# tmc2209.net
KiCad netlist of a schematic drawn in EAGLE
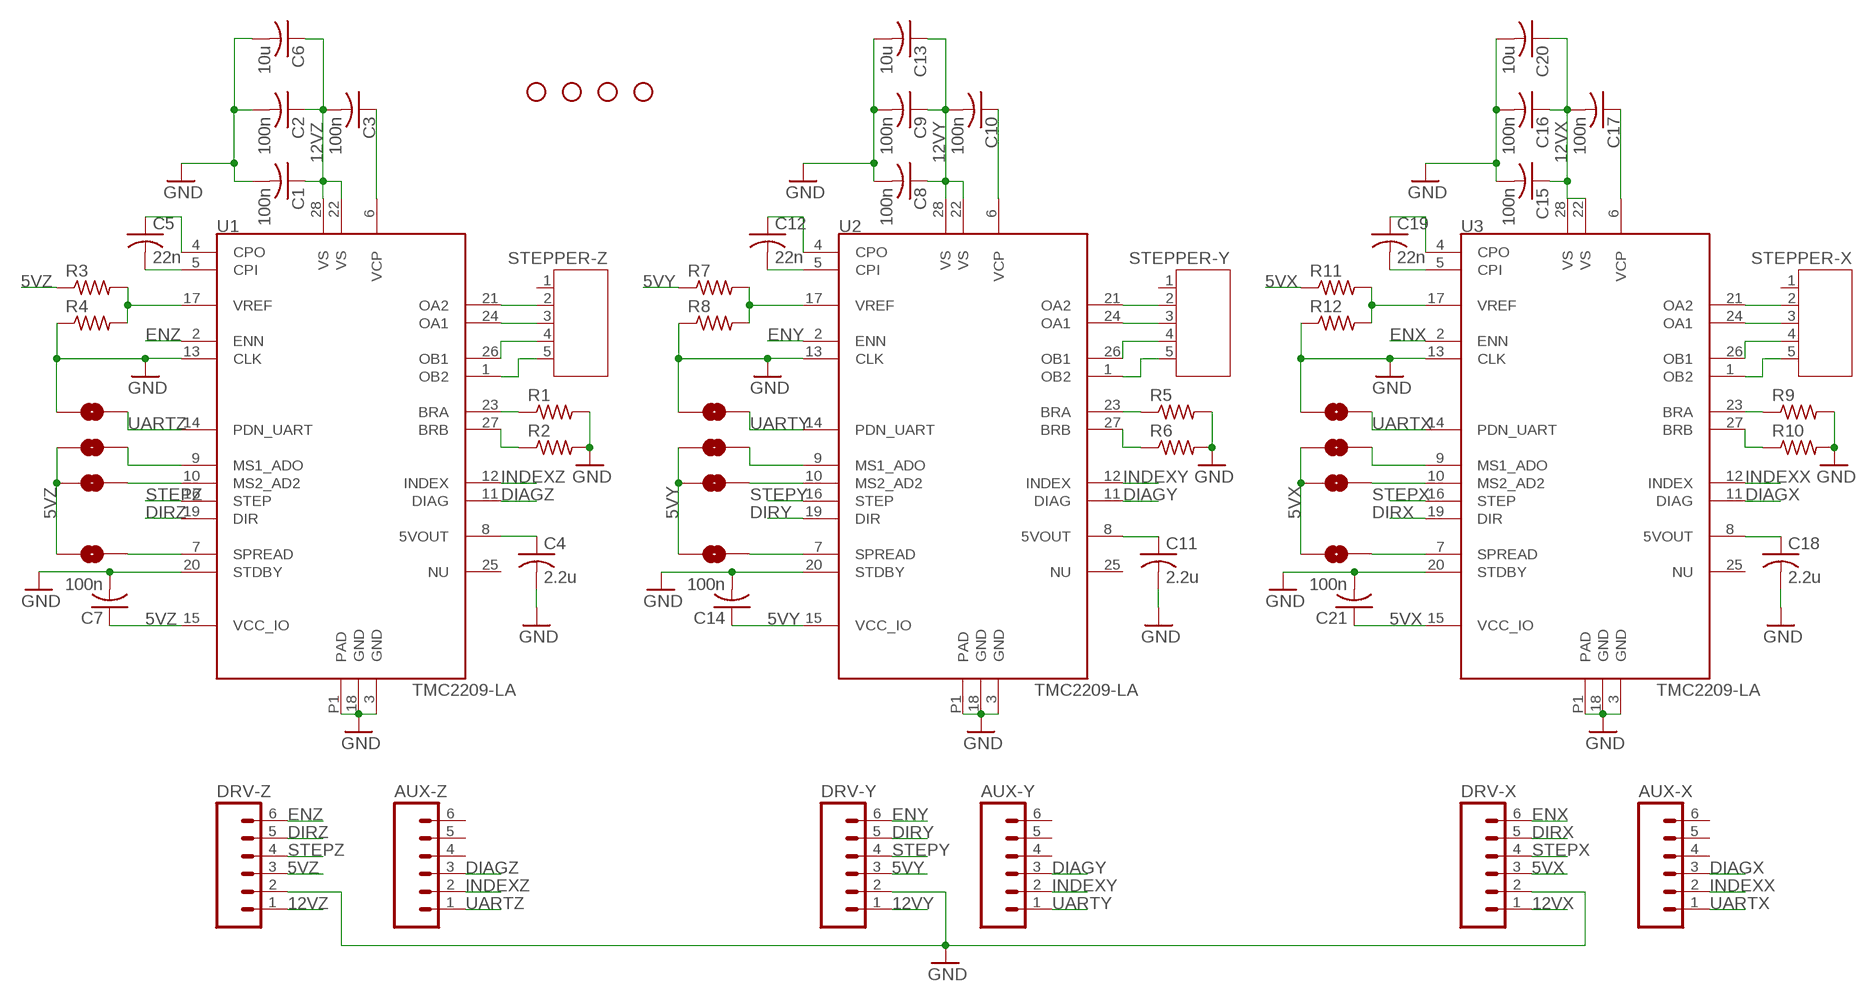
[diagram p0: schematic, sheet 1]

(export (version "E")
  (design (tool "Eeschema 10.0.6"))
  (components
    (comp (ref "AUX-X")
      (value "M06LOCK")
      (footprint "eagle-import:1X06_LOCK")
      (libsource (lib "eagle-import") (part "M06LOCK"))
    )
    (comp (ref "AUX-Y")
      (value "M06LOCK")
      (footprint "eagle-import:1X06_LOCK")
      (libsource (lib "eagle-import") (part "M06LOCK"))
    )
    (comp (ref "AUX-Z")
      (value "M06LOCK")
      (footprint "eagle-import:1X06_LOCK")
      (libsource (lib "eagle-import") (part "M06LOCK"))
    )
    (comp (ref "C1")
      (value "100n")
      (footprint "eagle-import:C0603")
      (libsource (lib "eagle-import") (part "C-USC0603"))
    )
    (comp (ref "C2")
      (value "100n")
      (footprint "eagle-import:C0603")
      (libsource (lib "eagle-import") (part "C-USC0603"))
    )
    (comp (ref "C3")
      (value "100n")
      (footprint "eagle-import:C0603")
      (libsource (lib "eagle-import") (part "C-USC0603"))
    )
    (comp (ref "C4")
      (value "2.2u")
      (footprint "eagle-import:C1206")
      (libsource (lib "eagle-import") (part "C-USC1206"))
    )
    (comp (ref "C5")
      (value "22n")
      (footprint "eagle-import:C0603")
      (libsource (lib "eagle-import") (part "C-USC0603"))
    )
    (comp (ref "C6")
      (value "10u")
      (footprint "eagle-import:C1206")
      (libsource (lib "eagle-import") (part "C-USC1206"))
    )
    (comp (ref "C7")
      (value "100n")
      (footprint "eagle-import:C0603")
      (libsource (lib "eagle-import") (part "C-USC0603"))
    )
    (comp (ref "C8")
      (value "100n")
      (footprint "eagle-import:C0603")
      (libsource (lib "eagle-import") (part "C-USC0603"))
    )
    (comp (ref "C9")
      (value "100n")
      (footprint "eagle-import:C0603")
      (libsource (lib "eagle-import") (part "C-USC0603"))
    )
    (comp (ref "C10")
      (value "100n")
      (footprint "eagle-import:C0603")
      (libsource (lib "eagle-import") (part "C-USC0603"))
    )
    (comp (ref "C11")
      (value "2.2u")
      (footprint "eagle-import:C1206")
      (libsource (lib "eagle-import") (part "C-USC1206"))
    )
    (comp (ref "C12")
      (value "22n")
      (footprint "eagle-import:C0603")
      (libsource (lib "eagle-import") (part "C-USC0603"))
    )
    (comp (ref "C13")
      (value "10u")
      (footprint "eagle-import:C1206")
      (libsource (lib "eagle-import") (part "C-USC1206"))
    )
    (comp (ref "C14")
      (value "100n")
      (footprint "eagle-import:C0603")
      (libsource (lib "eagle-import") (part "C-USC0603"))
    )
    (comp (ref "C15")
      (value "100n")
      (footprint "eagle-import:C0603")
      (libsource (lib "eagle-import") (part "C-USC0603"))
    )
    (comp (ref "C16")
      (value "100n")
      (footprint "eagle-import:C0603")
      (libsource (lib "eagle-import") (part "C-USC0603"))
    )
    (comp (ref "C17")
      (value "100n")
      (footprint "eagle-import:C0603")
      (libsource (lib "eagle-import") (part "C-USC0603"))
    )
    (comp (ref "C18")
      (value "2.2u")
      (footprint "eagle-import:C1206")
      (libsource (lib "eagle-import") (part "C-USC1206"))
    )
    (comp (ref "C19")
      (value "22n")
      (footprint "eagle-import:C0603")
      (libsource (lib "eagle-import") (part "C-USC0603"))
    )
    (comp (ref "C20")
      (value "10u")
      (footprint "eagle-import:C1206")
      (libsource (lib "eagle-import") (part "C-USC1206"))
    )
    (comp (ref "C21")
      (value "100n")
      (footprint "eagle-import:C0603")
      (libsource (lib "eagle-import") (part "C-USC0603"))
    )
    (comp (ref "DRV-X")
      (value "M06LOCK")
      (footprint "eagle-import:1X06_LOCK")
      (libsource (lib "eagle-import") (part "M06LOCK"))
    )
    (comp (ref "DRV-Y")
      (value "M06LOCK")
      (footprint "eagle-import:1X06_LOCK")
      (libsource (lib "eagle-import") (part "M06LOCK"))
    )
    (comp (ref "DRV-Z")
      (value "M06LOCK")
      (footprint "eagle-import:1X06_LOCK")
      (libsource (lib "eagle-import") (part "M06LOCK"))
    )
    (comp (ref "PDX")
      (value "SOLDERJUMPERNO")
      (footprint "eagle-import:SJ_2S-NO")
      (libsource (lib "eagle-import") (part "SOLDERJUMPERNO"))
    )
    (comp (ref "PDY")
      (value "SOLDERJUMPERNO")
      (footprint "eagle-import:SJ_2S-NO")
      (libsource (lib "eagle-import") (part "SOLDERJUMPERNO"))
    )
    (comp (ref "PDZ")
      (value "SOLDERJUMPERNO")
      (footprint "eagle-import:SJ_2S-NO")
      (libsource (lib "eagle-import") (part "SOLDERJUMPERNO"))
    )
    (comp (ref "R1")
      (value "R-US_R0805")
      (footprint "eagle-import:R0805")
      (libsource (lib "eagle-import") (part "R-US_R0805"))
    )
    (comp (ref "R2")
      (value "R-US_R0805")
      (footprint "eagle-import:R0805")
      (libsource (lib "eagle-import") (part "R-US_R0805"))
    )
    (comp (ref "R3")
      (value "R-US_R0603")
      (footprint "eagle-import:R0603")
      (libsource (lib "eagle-import") (part "R-US_R0603"))
    )
    (comp (ref "R4")
      (value "R-US_R0603")
      (footprint "eagle-import:R0603")
      (libsource (lib "eagle-import") (part "R-US_R0603"))
    )
    (comp (ref "R5")
      (value "R-US_R0805")
      (footprint "eagle-import:R0805")
      (libsource (lib "eagle-import") (part "R-US_R0805"))
    )
    (comp (ref "R6")
      (value "R-US_R0805")
      (footprint "eagle-import:R0805")
      (libsource (lib "eagle-import") (part "R-US_R0805"))
    )
    (comp (ref "R7")
      (value "R-US_R0603")
      (footprint "eagle-import:R0603")
      (libsource (lib "eagle-import") (part "R-US_R0603"))
    )
    (comp (ref "R8")
      (value "R-US_R0603")
      (footprint "eagle-import:R0603")
      (libsource (lib "eagle-import") (part "R-US_R0603"))
    )
    (comp (ref "R9")
      (value "R-US_R0805")
      (footprint "eagle-import:R0805")
      (libsource (lib "eagle-import") (part "R-US_R0805"))
    )
    (comp (ref "R10")
      (value "R-US_R0805")
      (footprint "eagle-import:R0805")
      (libsource (lib "eagle-import") (part "R-US_R0805"))
    )
    (comp (ref "R11")
      (value "R-US_R0603")
      (footprint "eagle-import:R0603")
      (libsource (lib "eagle-import") (part "R-US_R0603"))
    )
    (comp (ref "R12")
      (value "R-US_R0603")
      (footprint "eagle-import:R0603")
      (libsource (lib "eagle-import") (part "R-US_R0603"))
    )
    (comp (ref "SJ2")
      (value "SOLDERJUMPERNO")
      (footprint "eagle-import:SJ_2S-NO")
      (libsource (lib "eagle-import") (part "SOLDERJUMPERNO"))
    )
    (comp (ref "SJ3")
      (value "SOLDERJUMPERNO")
      (footprint "eagle-import:SJ_2S-NO")
      (libsource (lib "eagle-import") (part "SOLDERJUMPERNO"))
    )
    (comp (ref "SJ5")
      (value "SOLDERJUMPERNO")
      (footprint "eagle-import:SJ_2S-NO")
      (libsource (lib "eagle-import") (part "SOLDERJUMPERNO"))
    )
    (comp (ref "SJ6")
      (value "SOLDERJUMPERNO")
      (footprint "eagle-import:SJ_2S-NO")
      (libsource (lib "eagle-import") (part "SOLDERJUMPERNO"))
    )
    (comp (ref "SJ8")
      (value "SOLDERJUMPERNO")
      (footprint "eagle-import:SJ_2S-NO")
      (libsource (lib "eagle-import") (part "SOLDERJUMPERNO"))
    )
    (comp (ref "SJ9")
      (value "SOLDERJUMPERNO")
      (footprint "eagle-import:SJ_2S-NO")
      (libsource (lib "eagle-import") (part "SOLDERJUMPERNO"))
    )
    (comp (ref "SJ10")
      (value "SOLDERJUMPERNO")
      (footprint "eagle-import:SJ_2S-NO")
      (libsource (lib "eagle-import") (part "SOLDERJUMPERNO"))
    )
    (comp (ref "SJ11")
      (value "SOLDERJUMPERNO")
      (footprint "eagle-import:SJ_2S-NO")
      (libsource (lib "eagle-import") (part "SOLDERJUMPERNO"))
    )
    (comp (ref "SJ12")
      (value "SOLDERJUMPERNO")
      (footprint "eagle-import:SJ_2S-NO")
      (libsource (lib "eagle-import") (part "SOLDERJUMPERNO"))
    )
    (comp (ref "STANDOFF1")
      (value "STAND-OFFTIGHT")
      (footprint "eagle-import:STAND-OFF-TIGHT")
      (libsource (lib "eagle-import") (part "STAND-OFFTIGHT"))
    )
    (comp (ref "STANDOFF2")
      (value "STAND-OFFTIGHT")
      (footprint "eagle-import:STAND-OFF-TIGHT")
      (libsource (lib "eagle-import") (part "STAND-OFFTIGHT"))
    )
    (comp (ref "STANDOFF3")
      (value "STAND-OFFTIGHT")
      (footprint "eagle-import:STAND-OFF-TIGHT")
      (libsource (lib "eagle-import") (part "STAND-OFFTIGHT"))
    )
    (comp (ref "STANDOFF4")
      (value "STAND-OFFTIGHT")
      (footprint "eagle-import:STAND-OFF-TIGHT")
      (libsource (lib "eagle-import") (part "STAND-OFFTIGHT"))
    )
    (comp (ref "STEPPER-X")
      (value "JST-PH5")
      (footprint "eagle-import:JST-PH5")
      (libsource (lib "eagle-import") (part "JST-PH5"))
    )
    (comp (ref "STEPPER-Y")
      (value "JST-PH5")
      (footprint "eagle-import:JST-PH5")
      (libsource (lib "eagle-import") (part "JST-PH5"))
    )
    (comp (ref "STEPPER-Z")
      (value "JST-PH5")
      (footprint "eagle-import:JST-PH5")
      (libsource (lib "eagle-import") (part "JST-PH5"))
    )
    (comp (ref "U1")
      (value "TMC2209-LA")
      (footprint "eagle-import:QFN28-5X5-XLEP")
      (libsource (lib "eagle-import") (part "TMC2209-LA"))
    )
    (comp (ref "U2")
      (value "TMC2209-LA")
      (footprint "eagle-import:QFN28-5X5-XLEP")
      (libsource (lib "eagle-import") (part "TMC2209-LA"))
    )
    (comp (ref "U3")
      (value "TMC2209-LA")
      (footprint "eagle-import:QFN28-5X5-XLEP")
      (libsource (lib "eagle-import") (part "TMC2209-LA"))
    )
  )
  (nets
    (net (code "1") (name "/5VX") (class "Default")
      (node (ref "C21") (pin "1") (pinfunction "1_1") (pintype "passive"))
      (node (ref "DRV-X") (pin "3") (pinfunction "3_3") (pintype "passive"))
      (node (ref "R11") (pin "1") (pinfunction "1_1") (pintype "passive"))
      (node (ref "SJ12") (pin "1") (pinfunction "1_1") (pintype "passive"))
      (node (ref "SJ8") (pin "1") (pinfunction "1_1") (pintype "passive"))
      (node (ref "SJ9") (pin "1") (pinfunction "1_1") (pintype "passive"))
      (node (ref "U3") (pin "15") (pinfunction "VCC_IO_15") (pintype "bidirectional"))
    )
    (net (code "2") (name "/5VY") (class "Default")
      (node (ref "C14") (pin "1") (pinfunction "1_1") (pintype "passive"))
      (node (ref "DRV-Y") (pin "3") (pinfunction "3_3") (pintype "passive"))
      (node (ref "R7") (pin "1") (pinfunction "1_1") (pintype "passive"))
      (node (ref "SJ11") (pin "1") (pinfunction "1_1") (pintype "passive"))
      (node (ref "SJ5") (pin "1") (pinfunction "1_1") (pintype "passive"))
      (node (ref "SJ6") (pin "1") (pinfunction "1_1") (pintype "passive"))
      (node (ref "U2") (pin "15") (pinfunction "VCC_IO_15") (pintype "bidirectional"))
    )
    (net (code "3") (name "/5VZ") (class "Default")
      (node (ref "C7") (pin "1") (pinfunction "1_1") (pintype "passive"))
      (node (ref "DRV-Z") (pin "3") (pinfunction "3_3") (pintype "passive"))
      (node (ref "R3") (pin "1") (pinfunction "1_1") (pintype "passive"))
      (node (ref "SJ10") (pin "1") (pinfunction "1_1") (pintype "passive"))
      (node (ref "SJ2") (pin "1") (pinfunction "1_1") (pintype "passive"))
      (node (ref "SJ3") (pin "1") (pinfunction "1_1") (pintype "passive"))
      (node (ref "U1") (pin "15") (pinfunction "VCC_IO_15") (pintype "bidirectional"))
    )
    (net (code "4") (name "/12VX") (class "Default")
      (node (ref "C15") (pin "1") (pinfunction "1_1") (pintype "passive"))
      (node (ref "C16") (pin "1") (pinfunction "1_1") (pintype "passive"))
      (node (ref "C17") (pin "2") (pinfunction "2_2") (pintype "passive"))
      (node (ref "C20") (pin "1") (pinfunction "1_1") (pintype "passive"))
      (node (ref "DRV-X") (pin "1") (pinfunction "1_1") (pintype "passive"))
      (node (ref "U3") (pin "22") (pinfunction "VS_22") (pintype "bidirectional"))
      (node (ref "U3") (pin "28") (pinfunction "VS_28") (pintype "bidirectional"))
    )
    (net (code "5") (name "/12VY") (class "Default")
      (node (ref "C10") (pin "2") (pinfunction "2_2") (pintype "passive"))
      (node (ref "C13") (pin "1") (pinfunction "1_1") (pintype "passive"))
      (node (ref "C8") (pin "1") (pinfunction "1_1") (pintype "passive"))
      (node (ref "C9") (pin "1") (pinfunction "1_1") (pintype "passive"))
      (node (ref "DRV-Y") (pin "1") (pinfunction "1_1") (pintype "passive"))
      (node (ref "U2") (pin "22") (pinfunction "VS_22") (pintype "bidirectional"))
      (node (ref "U2") (pin "28") (pinfunction "VS_28") (pintype "bidirectional"))
    )
    (net (code "6") (name "/12VZ") (class "Default")
      (node (ref "C1") (pin "1") (pinfunction "1_1") (pintype "passive"))
      (node (ref "C2") (pin "1") (pinfunction "1_1") (pintype "passive"))
      (node (ref "C3") (pin "2") (pinfunction "2_2") (pintype "passive"))
      (node (ref "C6") (pin "1") (pinfunction "1_1") (pintype "passive"))
      (node (ref "DRV-Z") (pin "1") (pinfunction "1_1") (pintype "passive"))
      (node (ref "U1") (pin "22") (pinfunction "VS_22") (pintype "bidirectional"))
      (node (ref "U1") (pin "28") (pinfunction "VS_28") (pintype "bidirectional"))
    )
    (net (code "7") (name "/DIAGX") (class "Default")
      (node (ref "AUX-X") (pin "3") (pinfunction "3_3") (pintype "passive"))
      (node (ref "U3") (pin "11") (pinfunction "DIAG_11") (pintype "bidirectional"))
    )
    (net (code "8") (name "/DIAGY") (class "Default")
      (node (ref "AUX-Y") (pin "3") (pinfunction "3_3") (pintype "passive"))
      (node (ref "U2") (pin "11") (pinfunction "DIAG_11") (pintype "bidirectional"))
    )
    (net (code "9") (name "/DIAGZ") (class "Default")
      (node (ref "AUX-Z") (pin "3") (pinfunction "3_3") (pintype "passive"))
      (node (ref "U1") (pin "11") (pinfunction "DIAG_11") (pintype "bidirectional"))
    )
    (net (code "10") (name "/DIRX") (class "Default")
      (node (ref "DRV-X") (pin "5") (pinfunction "5_5") (pintype "passive"))
      (node (ref "U3") (pin "19") (pinfunction "DIR_19") (pintype "bidirectional"))
    )
    (net (code "11") (name "/DIRY") (class "Default")
      (node (ref "DRV-Y") (pin "5") (pinfunction "5_5") (pintype "passive"))
      (node (ref "U2") (pin "19") (pinfunction "DIR_19") (pintype "bidirectional"))
    )
    (net (code "12") (name "/DIRZ") (class "Default")
      (node (ref "DRV-Z") (pin "5") (pinfunction "5_5") (pintype "passive"))
      (node (ref "U1") (pin "19") (pinfunction "DIR_19") (pintype "bidirectional"))
    )
    (net (code "13") (name "/ENX") (class "Default")
      (node (ref "DRV-X") (pin "6") (pinfunction "6_6") (pintype "passive"))
      (node (ref "U3") (pin "2") (pinfunction "ENN_2") (pintype "bidirectional"))
    )
    (net (code "14") (name "/ENY") (class "Default")
      (node (ref "DRV-Y") (pin "6") (pinfunction "6_6") (pintype "passive"))
      (node (ref "U2") (pin "2") (pinfunction "ENN_2") (pintype "bidirectional"))
    )
    (net (code "15") (name "/ENZ") (class "Default")
      (node (ref "DRV-Z") (pin "6") (pinfunction "6_6") (pintype "passive"))
      (node (ref "U1") (pin "2") (pinfunction "ENN_2") (pintype "bidirectional"))
    )
    (net (code "16") (name "/INDEXX") (class "Default")
      (node (ref "AUX-X") (pin "2") (pinfunction "2_2") (pintype "passive"))
      (node (ref "U3") (pin "12") (pinfunction "INDEX_12") (pintype "bidirectional"))
    )
    (net (code "17") (name "/INDEXY") (class "Default")
      (node (ref "AUX-Y") (pin "2") (pinfunction "2_2") (pintype "passive"))
      (node (ref "U2") (pin "12") (pinfunction "INDEX_12") (pintype "bidirectional"))
    )
    (net (code "18") (name "/INDEXZ") (class "Default")
      (node (ref "AUX-Z") (pin "2") (pinfunction "2_2") (pintype "passive"))
      (node (ref "U1") (pin "12") (pinfunction "INDEX_12") (pintype "bidirectional"))
    )
    (net (code "19") (name "/STEPX") (class "Default")
      (node (ref "DRV-X") (pin "4") (pinfunction "4_4") (pintype "passive"))
      (node (ref "U3") (pin "16") (pinfunction "STEP_16") (pintype "bidirectional"))
    )
    (net (code "20") (name "/STEPY") (class "Default")
      (node (ref "DRV-Y") (pin "4") (pinfunction "4_4") (pintype "passive"))
      (node (ref "U2") (pin "16") (pinfunction "STEP_16") (pintype "bidirectional"))
    )
    (net (code "21") (name "/STEPZ") (class "Default")
      (node (ref "DRV-Z") (pin "4") (pinfunction "4_4") (pintype "passive"))
      (node (ref "U1") (pin "16") (pinfunction "STEP_16") (pintype "bidirectional"))
    )
    (net (code "22") (name "/UARTX") (class "Default")
      (node (ref "AUX-X") (pin "1") (pinfunction "1_1") (pintype "passive"))
      (node (ref "PDX") (pin "2") (pinfunction "2_2") (pintype "passive"))
      (node (ref "U3") (pin "14") (pinfunction "PDN_UART_14") (pintype "bidirectional"))
    )
    (net (code "23") (name "/UARTY") (class "Default")
      (node (ref "AUX-Y") (pin "1") (pinfunction "1_1") (pintype "passive"))
      (node (ref "PDY") (pin "2") (pinfunction "2_2") (pintype "passive"))
      (node (ref "U2") (pin "14") (pinfunction "PDN_UART_14") (pintype "bidirectional"))
    )
    (net (code "24") (name "/UARTZ") (class "Default")
      (node (ref "AUX-Z") (pin "1") (pinfunction "1_1") (pintype "passive"))
      (node (ref "PDZ") (pin "2") (pinfunction "2_2") (pintype "passive"))
      (node (ref "U1") (pin "14") (pinfunction "PDN_UART_14") (pintype "bidirectional"))
    )
    (net (code "25") (name "GND") (class "Default")
      (node (ref "C1") (pin "2") (pinfunction "2_2") (pintype "passive"))
      (node (ref "C11") (pin "2") (pinfunction "2_2") (pintype "passive"))
      (node (ref "C13") (pin "2") (pinfunction "2_2") (pintype "passive"))
      (node (ref "C14") (pin "2") (pinfunction "2_2") (pintype "passive"))
      (node (ref "C15") (pin "2") (pinfunction "2_2") (pintype "passive"))
      (node (ref "C16") (pin "2") (pinfunction "2_2") (pintype "passive"))
      (node (ref "C18") (pin "2") (pinfunction "2_2") (pintype "passive"))
      (node (ref "C2") (pin "2") (pinfunction "2_2") (pintype "passive"))
      (node (ref "C20") (pin "2") (pinfunction "2_2") (pintype "passive"))
      (node (ref "C21") (pin "2") (pinfunction "2_2") (pintype "passive"))
      (node (ref "C4") (pin "2") (pinfunction "2_2") (pintype "passive"))
      (node (ref "C6") (pin "2") (pinfunction "2_2") (pintype "passive"))
      (node (ref "C7") (pin "2") (pinfunction "2_2") (pintype "passive"))
      (node (ref "C8") (pin "2") (pinfunction "2_2") (pintype "passive"))
      (node (ref "C9") (pin "2") (pinfunction "2_2") (pintype "passive"))
      (node (ref "DRV-X") (pin "2") (pinfunction "2_2") (pintype "passive"))
      (node (ref "DRV-Y") (pin "2") (pinfunction "2_2") (pintype "passive"))
      (node (ref "DRV-Z") (pin "2") (pinfunction "2_2") (pintype "passive"))
      (node (ref "PDX") (pin "1") (pinfunction "1_1") (pintype "passive"))
      (node (ref "PDY") (pin "1") (pinfunction "1_1") (pintype "passive"))
      (node (ref "PDZ") (pin "1") (pinfunction "1_1") (pintype "passive"))
      (node (ref "R1") (pin "2") (pinfunction "2_2") (pintype "passive"))
      (node (ref "R10") (pin "2") (pinfunction "2_2") (pintype "passive"))
      (node (ref "R12") (pin "1") (pinfunction "1_1") (pintype "passive"))
      (node (ref "R2") (pin "2") (pinfunction "2_2") (pintype "passive"))
      (node (ref "R4") (pin "1") (pinfunction "1_1") (pintype "passive"))
      (node (ref "R5") (pin "2") (pinfunction "2_2") (pintype "passive"))
      (node (ref "R6") (pin "2") (pinfunction "2_2") (pintype "passive"))
      (node (ref "R8") (pin "1") (pinfunction "1_1") (pintype "passive"))
      (node (ref "R9") (pin "2") (pinfunction "2_2") (pintype "passive"))
      (node (ref "U1") (pin "13") (pinfunction "CLK_13") (pintype "bidirectional"))
      (node (ref "U1") (pin "18") (pinfunction "GND_18") (pintype "bidirectional"))
      (node (ref "U1") (pin "20") (pinfunction "STDBY_20") (pintype "bidirectional"))
      (node (ref "U1") (pin "3") (pinfunction "GND_3") (pintype "bidirectional"))
      (node (ref "U1") (pin "P1") (pinfunction "PAD_P1") (pintype "bidirectional"))
      (node (ref "U2") (pin "13") (pinfunction "CLK_13") (pintype "bidirectional"))
      (node (ref "U2") (pin "18") (pinfunction "GND_18") (pintype "bidirectional"))
      (node (ref "U2") (pin "20") (pinfunction "STDBY_20") (pintype "bidirectional"))
      (node (ref "U2") (pin "3") (pinfunction "GND_3") (pintype "bidirectional"))
      (node (ref "U2") (pin "P1") (pinfunction "PAD_P1") (pintype "bidirectional"))
      (node (ref "U3") (pin "13") (pinfunction "CLK_13") (pintype "bidirectional"))
      (node (ref "U3") (pin "18") (pinfunction "GND_18") (pintype "bidirectional"))
      (node (ref "U3") (pin "20") (pinfunction "STDBY_20") (pintype "bidirectional"))
      (node (ref "U3") (pin "3") (pinfunction "GND_3") (pintype "bidirectional"))
      (node (ref "U3") (pin "P1") (pinfunction "PAD_P1") (pintype "bidirectional"))
    )
    (net (code "26") (name "Net-(U1-5VOUT)") (class "Default")
      (node (ref "C4") (pin "1") (pinfunction "1_1") (pintype "passive"))
      (node (ref "U1") (pin "8") (pinfunction "5VOUT_8") (pintype "bidirectional"))
    )
    (net (code "27") (name "Net-(U1-BRA)") (class "Default")
      (node (ref "R1") (pin "1") (pinfunction "1_1") (pintype "passive"))
      (node (ref "U1") (pin "23") (pinfunction "BRA_23") (pintype "bidirectional"))
    )
    (net (code "28") (name "Net-(U1-BRB)") (class "Default")
      (node (ref "R2") (pin "1") (pinfunction "1_1") (pintype "passive"))
      (node (ref "U1") (pin "27") (pinfunction "BRB_27") (pintype "bidirectional"))
    )
    (net (code "29") (name "Net-(U1-CPI)") (class "Default")
      (node (ref "C5") (pin "2") (pinfunction "2_2") (pintype "passive"))
      (node (ref "U1") (pin "5") (pinfunction "CPI_5") (pintype "bidirectional"))
    )
    (net (code "30") (name "Net-(U1-CPO)") (class "Default")
      (node (ref "C5") (pin "1") (pinfunction "1_1") (pintype "passive"))
      (node (ref "U1") (pin "4") (pinfunction "CPO_4") (pintype "bidirectional"))
    )
    (net (code "31") (name "Net-(U1-MS1_ADO)") (class "Default")
      (node (ref "SJ2") (pin "2") (pinfunction "2_2") (pintype "passive"))
      (node (ref "U1") (pin "9") (pinfunction "MS1_ADO_9") (pintype "bidirectional"))
    )
    (net (code "32") (name "Net-(U1-MS2_AD2)") (class "Default")
      (node (ref "SJ3") (pin "2") (pinfunction "2_2") (pintype "passive"))
      (node (ref "U1") (pin "10") (pinfunction "MS2_AD2_10") (pintype "bidirectional"))
    )
    (net (code "33") (name "Net-(U1-OA1)") (class "Default")
      (node (ref "STEPPER-Z") (pin "3") (pinfunction "3_3") (pintype "passive"))
      (node (ref "U1") (pin "24") (pinfunction "OA1_24") (pintype "bidirectional"))
    )
    (net (code "34") (name "Net-(U1-OA2)") (class "Default")
      (node (ref "STEPPER-Z") (pin "2") (pinfunction "2_2") (pintype "passive"))
      (node (ref "U1") (pin "21") (pinfunction "OA2_21") (pintype "bidirectional"))
    )
    (net (code "35") (name "Net-(U1-OB1)") (class "Default")
      (node (ref "STEPPER-Z") (pin "4") (pinfunction "4_4") (pintype "passive"))
      (node (ref "U1") (pin "26") (pinfunction "OB1_26") (pintype "bidirectional"))
    )
    (net (code "36") (name "Net-(U1-OB2)") (class "Default")
      (node (ref "STEPPER-Z") (pin "5") (pinfunction "5_5") (pintype "passive"))
      (node (ref "U1") (pin "1") (pinfunction "OB2_1") (pintype "bidirectional"))
    )
    (net (code "37") (name "Net-(U1-SPREAD)") (class "Default")
      (node (ref "SJ10") (pin "2") (pinfunction "2_2") (pintype "passive"))
      (node (ref "U1") (pin "7") (pinfunction "SPREAD_7") (pintype "bidirectional"))
    )
    (net (code "38") (name "Net-(U1-VCP)") (class "Default")
      (node (ref "C3") (pin "1") (pinfunction "1_1") (pintype "passive"))
      (node (ref "U1") (pin "6") (pinfunction "VCP_6") (pintype "bidirectional"))
    )
    (net (code "39") (name "Net-(U1-VREF)") (class "Default")
      (node (ref "R3") (pin "2") (pinfunction "2_2") (pintype "passive"))
      (node (ref "R4") (pin "2") (pinfunction "2_2") (pintype "passive"))
      (node (ref "U1") (pin "17") (pinfunction "VREF_17") (pintype "bidirectional"))
    )
    (net (code "40") (name "Net-(U2-5VOUT)") (class "Default")
      (node (ref "C11") (pin "1") (pinfunction "1_1") (pintype "passive"))
      (node (ref "U2") (pin "8") (pinfunction "5VOUT_8") (pintype "bidirectional"))
    )
    (net (code "41") (name "Net-(U2-BRA)") (class "Default")
      (node (ref "R5") (pin "1") (pinfunction "1_1") (pintype "passive"))
      (node (ref "U2") (pin "23") (pinfunction "BRA_23") (pintype "bidirectional"))
    )
    (net (code "42") (name "Net-(U2-BRB)") (class "Default")
      (node (ref "R6") (pin "1") (pinfunction "1_1") (pintype "passive"))
      (node (ref "U2") (pin "27") (pinfunction "BRB_27") (pintype "bidirectional"))
    )
    (net (code "43") (name "Net-(U2-CPI)") (class "Default")
      (node (ref "C12") (pin "2") (pinfunction "2_2") (pintype "passive"))
      (node (ref "U2") (pin "5") (pinfunction "CPI_5") (pintype "bidirectional"))
    )
    (net (code "44") (name "Net-(U2-CPO)") (class "Default")
      (node (ref "C12") (pin "1") (pinfunction "1_1") (pintype "passive"))
      (node (ref "U2") (pin "4") (pinfunction "CPO_4") (pintype "bidirectional"))
    )
    (net (code "45") (name "Net-(U2-MS1_ADO)") (class "Default")
      (node (ref "SJ5") (pin "2") (pinfunction "2_2") (pintype "passive"))
      (node (ref "U2") (pin "9") (pinfunction "MS1_ADO_9") (pintype "bidirectional"))
    )
    (net (code "46") (name "Net-(U2-MS2_AD2)") (class "Default")
      (node (ref "SJ6") (pin "2") (pinfunction "2_2") (pintype "passive"))
      (node (ref "U2") (pin "10") (pinfunction "MS2_AD2_10") (pintype "bidirectional"))
    )
    (net (code "47") (name "Net-(U2-OA1)") (class "Default")
      (node (ref "STEPPER-Y") (pin "3") (pinfunction "3_3") (pintype "passive"))
      (node (ref "U2") (pin "24") (pinfunction "OA1_24") (pintype "bidirectional"))
    )
    (net (code "48") (name "Net-(U2-OA2)") (class "Default")
      (node (ref "STEPPER-Y") (pin "2") (pinfunction "2_2") (pintype "passive"))
      (node (ref "U2") (pin "21") (pinfunction "OA2_21") (pintype "bidirectional"))
    )
    (net (code "49") (name "Net-(U2-OB1)") (class "Default")
      (node (ref "STEPPER-Y") (pin "4") (pinfunction "4_4") (pintype "passive"))
      (node (ref "U2") (pin "26") (pinfunction "OB1_26") (pintype "bidirectional"))
    )
    (net (code "50") (name "Net-(U2-OB2)") (class "Default")
      (node (ref "STEPPER-Y") (pin "5") (pinfunction "5_5") (pintype "passive"))
      (node (ref "U2") (pin "1") (pinfunction "OB2_1") (pintype "bidirectional"))
    )
    (net (code "51") (name "Net-(U2-SPREAD)") (class "Default")
      (node (ref "SJ11") (pin "2") (pinfunction "2_2") (pintype "passive"))
      (node (ref "U2") (pin "7") (pinfunction "SPREAD_7") (pintype "bidirectional"))
    )
    (net (code "52") (name "Net-(U2-VCP)") (class "Default")
      (node (ref "C10") (pin "1") (pinfunction "1_1") (pintype "passive"))
      (node (ref "U2") (pin "6") (pinfunction "VCP_6") (pintype "bidirectional"))
    )
    (net (code "53") (name "Net-(U2-VREF)") (class "Default")
      (node (ref "R7") (pin "2") (pinfunction "2_2") (pintype "passive"))
      (node (ref "R8") (pin "2") (pinfunction "2_2") (pintype "passive"))
      (node (ref "U2") (pin "17") (pinfunction "VREF_17") (pintype "bidirectional"))
    )
    (net (code "54") (name "Net-(U3-5VOUT)") (class "Default")
      (node (ref "C18") (pin "1") (pinfunction "1_1") (pintype "passive"))
      (node (ref "U3") (pin "8") (pinfunction "5VOUT_8") (pintype "bidirectional"))
    )
    (net (code "55") (name "Net-(U3-BRA)") (class "Default")
      (node (ref "R9") (pin "1") (pinfunction "1_1") (pintype "passive"))
      (node (ref "U3") (pin "23") (pinfunction "BRA_23") (pintype "bidirectional"))
    )
    (net (code "56") (name "Net-(U3-BRB)") (class "Default")
      (node (ref "R10") (pin "1") (pinfunction "1_1") (pintype "passive"))
      (node (ref "U3") (pin "27") (pinfunction "BRB_27") (pintype "bidirectional"))
    )
    (net (code "57") (name "Net-(U3-CPI)") (class "Default")
      (node (ref "C19") (pin "2") (pinfunction "2_2") (pintype "passive"))
      (node (ref "U3") (pin "5") (pinfunction "CPI_5") (pintype "bidirectional"))
    )
    (net (code "58") (name "Net-(U3-CPO)") (class "Default")
      (node (ref "C19") (pin "1") (pinfunction "1_1") (pintype "passive"))
      (node (ref "U3") (pin "4") (pinfunction "CPO_4") (pintype "bidirectional"))
    )
    (net (code "59") (name "Net-(U3-MS1_ADO)") (class "Default")
      (node (ref "SJ8") (pin "2") (pinfunction "2_2") (pintype "passive"))
      (node (ref "U3") (pin "9") (pinfunction "MS1_ADO_9") (pintype "bidirectional"))
    )
    (net (code "60") (name "Net-(U3-MS2_AD2)") (class "Default")
      (node (ref "SJ9") (pin "2") (pinfunction "2_2") (pintype "passive"))
      (node (ref "U3") (pin "10") (pinfunction "MS2_AD2_10") (pintype "bidirectional"))
    )
    (net (code "61") (name "Net-(U3-OA1)") (class "Default")
      (node (ref "STEPPER-X") (pin "3") (pinfunction "3_3") (pintype "passive"))
      (node (ref "U3") (pin "24") (pinfunction "OA1_24") (pintype "bidirectional"))
    )
    (net (code "62") (name "Net-(U3-OA2)") (class "Default")
      (node (ref "STEPPER-X") (pin "2") (pinfunction "2_2") (pintype "passive"))
      (node (ref "U3") (pin "21") (pinfunction "OA2_21") (pintype "bidirectional"))
    )
    (net (code "63") (name "Net-(U3-OB1)") (class "Default")
      (node (ref "STEPPER-X") (pin "4") (pinfunction "4_4") (pintype "passive"))
      (node (ref "U3") (pin "26") (pinfunction "OB1_26") (pintype "bidirectional"))
    )
    (net (code "64") (name "Net-(U3-OB2)") (class "Default")
      (node (ref "STEPPER-X") (pin "5") (pinfunction "5_5") (pintype "passive"))
      (node (ref "U3") (pin "1") (pinfunction "OB2_1") (pintype "bidirectional"))
    )
    (net (code "65") (name "Net-(U3-SPREAD)") (class "Default")
      (node (ref "SJ12") (pin "2") (pinfunction "2_2") (pintype "passive"))
      (node (ref "U3") (pin "7") (pinfunction "SPREAD_7") (pintype "bidirectional"))
    )
    (net (code "66") (name "Net-(U3-VCP)") (class "Default")
      (node (ref "C17") (pin "1") (pinfunction "1_1") (pintype "passive"))
      (node (ref "U3") (pin "6") (pinfunction "VCP_6") (pintype "bidirectional"))
    )
    (net (code "67") (name "Net-(U3-VREF)") (class "Default")
      (node (ref "R11") (pin "2") (pinfunction "2_2") (pintype "passive"))
      (node (ref "R12") (pin "2") (pinfunction "2_2") (pintype "passive"))
      (node (ref "U3") (pin "17") (pinfunction "VREF_17") (pintype "bidirectional"))
    )
    (net (code "68") (name "unconnected-(AUX-X-Pad4)") (class "Default")
      (node (ref "AUX-X") (pin "4") (pinfunction "4_4") (pintype "passive"))
    )
    (net (code "69") (name "unconnected-(AUX-X-Pad5)") (class "Default")
      (node (ref "AUX-X") (pin "5") (pinfunction "5_5") (pintype "passive"))
    )
    (net (code "70") (name "unconnected-(AUX-X-Pad6)") (class "Default")
      (node (ref "AUX-X") (pin "6") (pinfunction "6_6") (pintype "passive"))
    )
    (net (code "71") (name "unconnected-(AUX-Y-Pad4)") (class "Default")
      (node (ref "AUX-Y") (pin "4") (pinfunction "4_4") (pintype "passive"))
    )
    (net (code "72") (name "unconnected-(AUX-Y-Pad5)") (class "Default")
      (node (ref "AUX-Y") (pin "5") (pinfunction "5_5") (pintype "passive"))
    )
    (net (code "73") (name "unconnected-(AUX-Y-Pad6)") (class "Default")
      (node (ref "AUX-Y") (pin "6") (pinfunction "6_6") (pintype "passive"))
    )
    (net (code "74") (name "unconnected-(AUX-Z-Pad4)") (class "Default")
      (node (ref "AUX-Z") (pin "4") (pinfunction "4_4") (pintype "passive"))
    )
    (net (code "75") (name "unconnected-(AUX-Z-Pad5)") (class "Default")
      (node (ref "AUX-Z") (pin "5") (pinfunction "5_5") (pintype "passive"))
    )
    (net (code "76") (name "unconnected-(AUX-Z-Pad6)") (class "Default")
      (node (ref "AUX-Z") (pin "6") (pinfunction "6_6") (pintype "passive"))
    )
    (net (code "77") (name "unconnected-(STEPPER-X-Pad1)") (class "Default")
      (node (ref "STEPPER-X") (pin "1") (pinfunction "1_1") (pintype "passive"))
    )
    (net (code "78") (name "unconnected-(STEPPER-Y-Pad1)") (class "Default")
      (node (ref "STEPPER-Y") (pin "1") (pinfunction "1_1") (pintype "passive"))
    )
    (net (code "79") (name "unconnected-(STEPPER-Z-Pad1)") (class "Default")
      (node (ref "STEPPER-Z") (pin "1") (pinfunction "1_1") (pintype "passive"))
    )
    (net (code "80") (name "unconnected-(U1-NU-Pad25)") (class "Default")
      (node (ref "U1") (pin "25") (pinfunction "NU_25") (pintype "bidirectional"))
    )
    (net (code "81") (name "unconnected-(U2-NU-Pad25)") (class "Default")
      (node (ref "U2") (pin "25") (pinfunction "NU_25") (pintype "bidirectional"))
    )
    (net (code "82") (name "unconnected-(U3-NU-Pad25)") (class "Default")
      (node (ref "U3") (pin "25") (pinfunction "NU_25") (pintype "bidirectional"))
    )
  )
)
